# SCH_GesPot_2025-03-14.net
KiCad netlist of a schematic drawn in EasyEDA
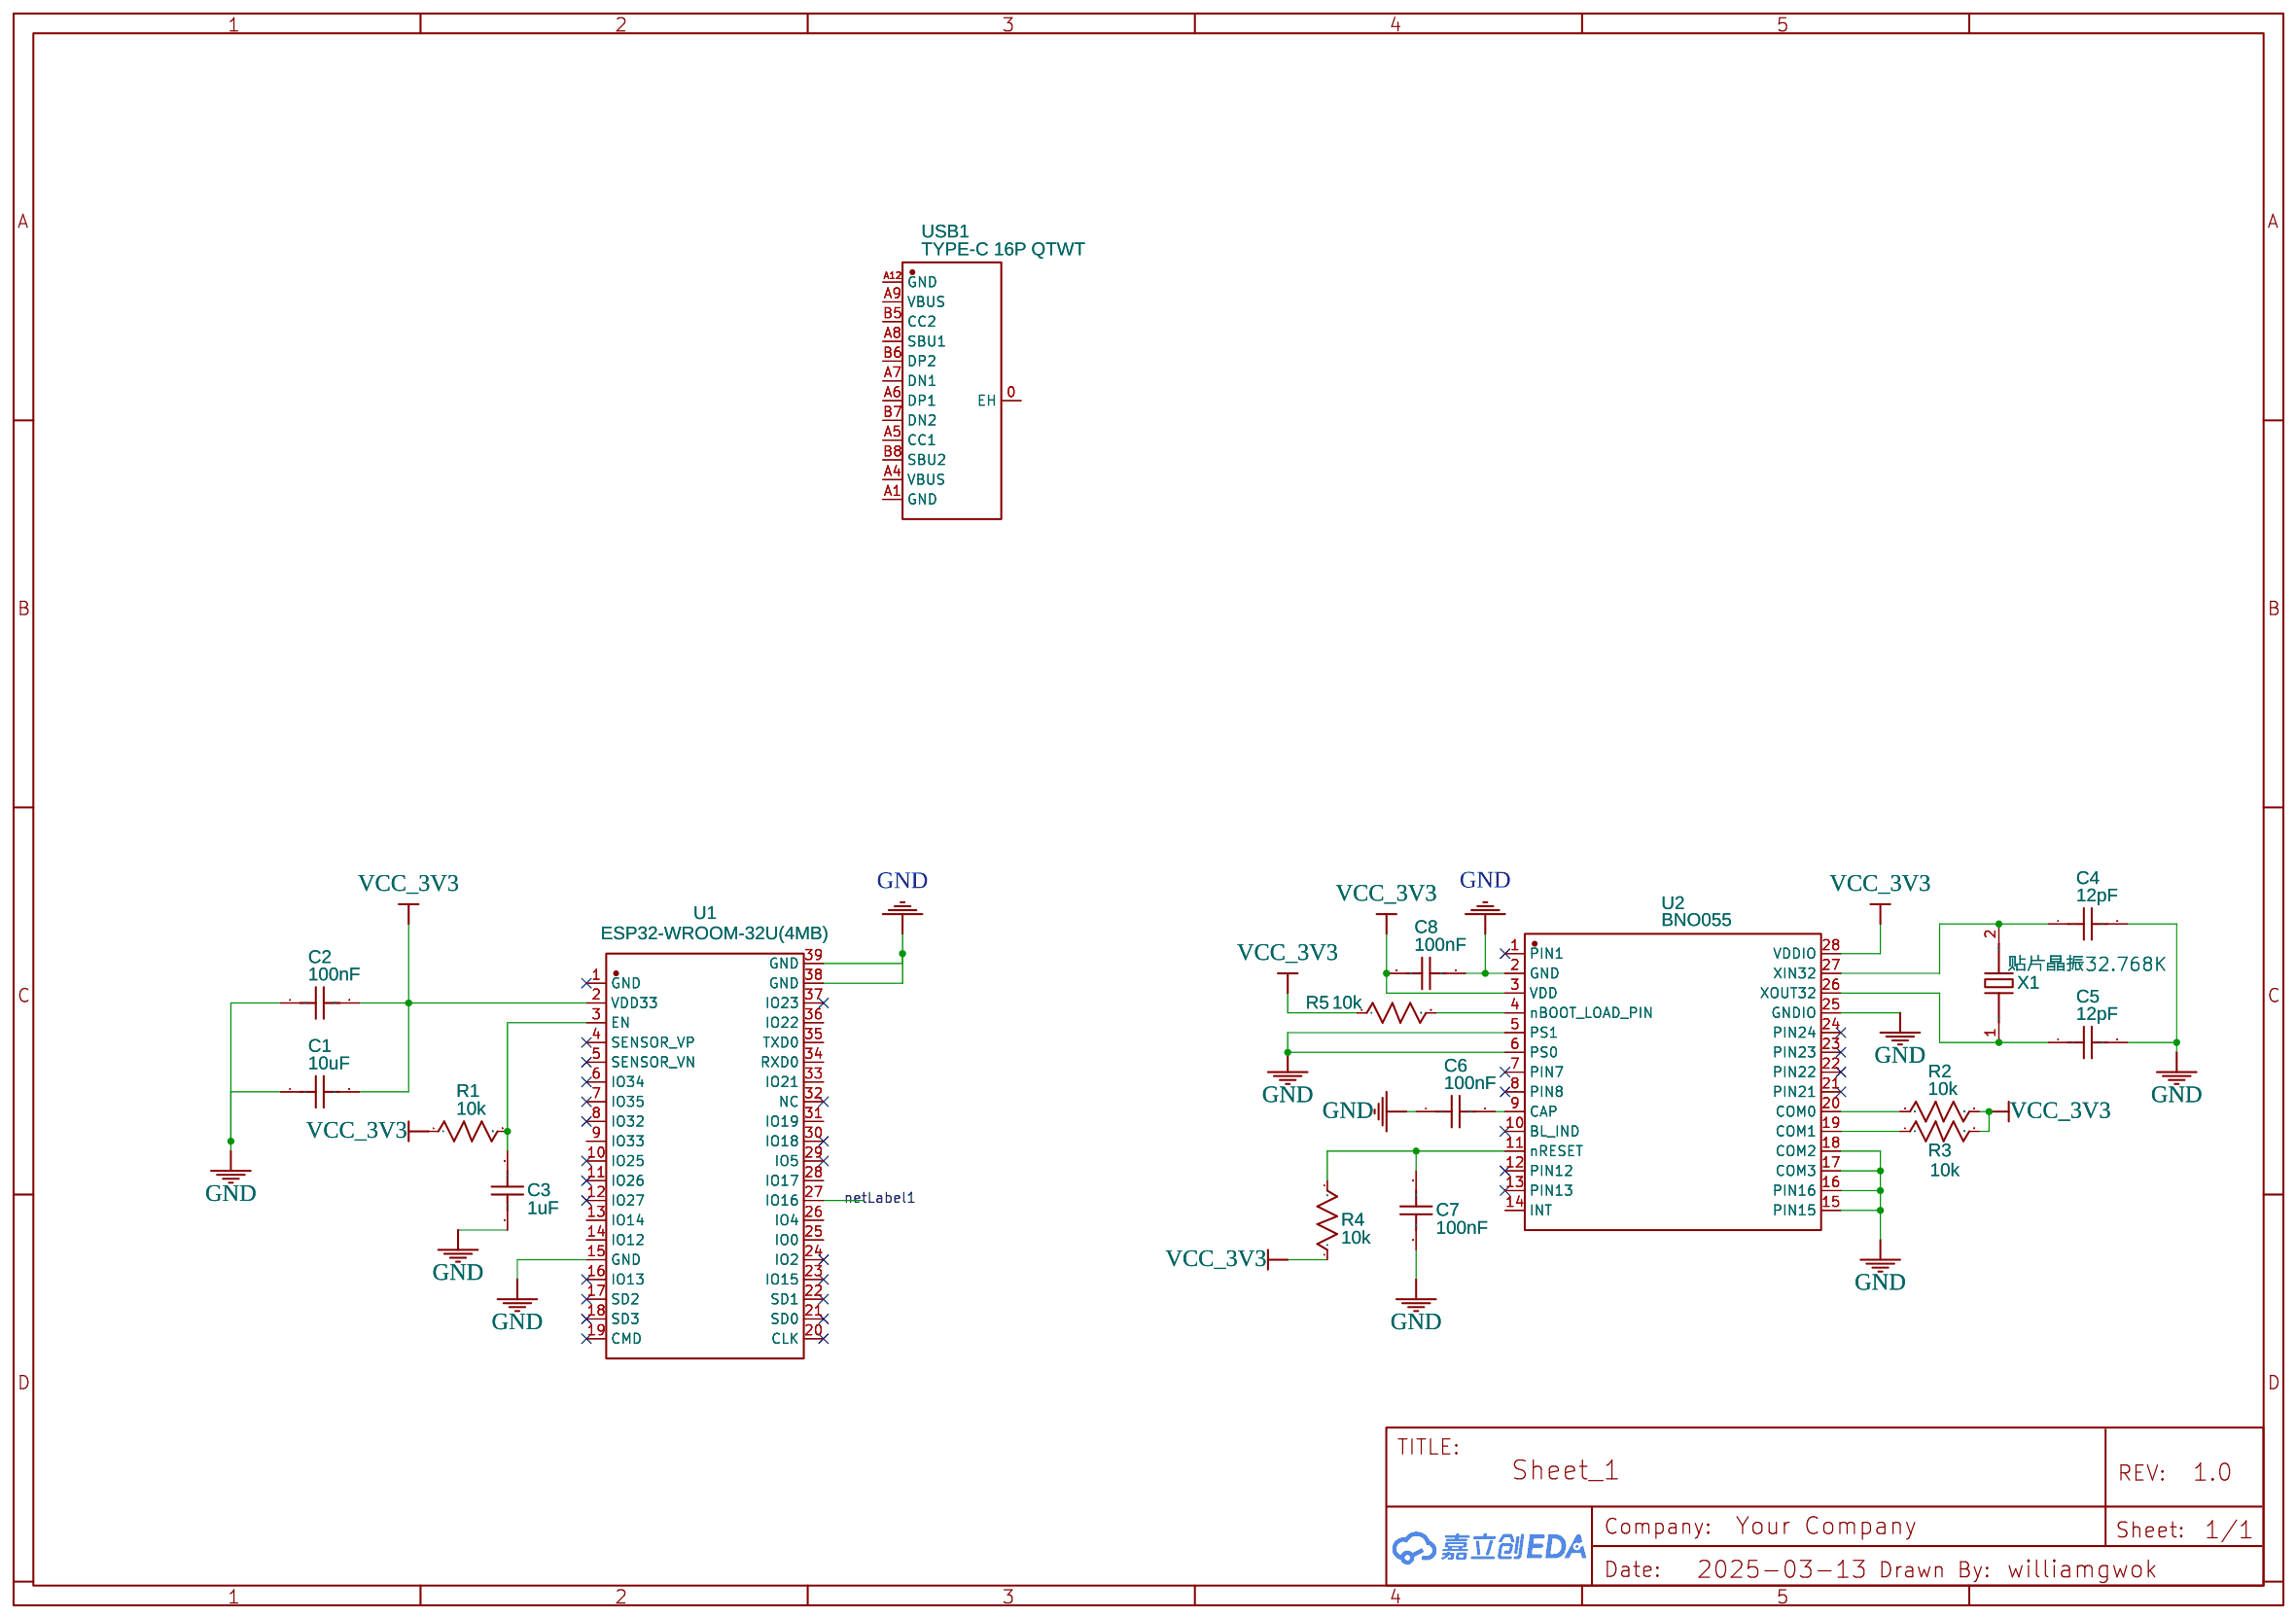
[diagram p0: schematic sheet]

(export (version "E")
  (design (tool "Eeschema 10.0.6"))
  (components
    (comp (ref "C1") (value "10uF") (libsource (lib "") (part "C_0603_US")))
    (comp (ref "C2") (value "100nF") (libsource (lib "") (part "C_0603_US")))
    (comp (ref "C3") (value "1uF") (libsource (lib "") (part "C_0603_US_2")))
    (comp (ref "C4") (value "12pF") (libsource (lib "") (part "C_0603_US")))
    (comp (ref "C5") (value "12pF") (libsource (lib "") (part "C_0603_US")))
    (comp (ref "C6") (value "100nF") (libsource (lib "") (part "C_0603_US")))
    (comp (ref "C7") (value "100nF") (libsource (lib "") (part "C_0603_US_2")))
    (comp (ref "C8") (value "100nF") (libsource (lib "") (part "C_0603_US_1")))
    (comp (ref "R1") (value "10k") (libsource (lib "") (part "R_0603_US")))
    (comp (ref "R2") (value "10k") (libsource (lib "") (part "R_0603_US")))
    (comp (ref "R3") (value "10k") (libsource (lib "") (part "R_0603_US")))
    (comp (ref "R4") (value "10k") (libsource (lib "") (part "R_0603_US_1")))
    (comp (ref "R5") (value "10k") (libsource (lib "") (part "R_0603_US")))
    (comp (ref "U1")
      (value "ESP32-WROOM-32U(4MB)")
      (fields (field (name "Manufacturer") "ESPRESSIF(乐鑫)"))
      (libsource (lib "") (part "ESP32-WROOM-32U(4MB)"))
    )
    (comp (ref "U2")
      (value "BNO055")
      (fields (field (name "Manufacturer") "Bosch(博世)"))
      (libsource (lib "") (part "BNO055"))
    )
    (comp (ref "USB1")
      (value "TYPE-C 16P QTWT")
      (fields (field (name "Manufacturer") "SHOU HAN(首韩)"))
      (libsource (lib "") (part "TYPE-C 16P QTWT"))
    )
    (comp (ref "X1")
      (value "贴片晶振32.768K")
      (fields (field (name "Manufacturer Part") "贴片晶振32.768k"))
      (libsource (lib "") (part "贴片晶振32.768K"))
    )
  )
  (nets
    (net (code "1") (name "/netLabel1") (class "Default")
      (node (ref "U1") (pin "27") (pinfunction "IO16_27") (pintype "unspecified"))
    )
    (net (code "2") (name "GND") (class "Default")
      (node (ref "C1") (pin "1") (pinfunction "1_1") (pintype "unspecified"))
      (node (ref "C2") (pin "1") (pinfunction "1_1") (pintype "unspecified"))
      (node (ref "C3") (pin "1") (pinfunction "1_1") (pintype "unspecified"))
      (node (ref "C4") (pin "2") (pinfunction "2_2") (pintype "unspecified"))
      (node (ref "C5") (pin "2") (pinfunction "2_2") (pintype "unspecified"))
      (node (ref "C6") (pin "1") (pinfunction "1_1") (pintype "unspecified"))
      (node (ref "C7") (pin "1") (pinfunction "1_1") (pintype "unspecified"))
      (node (ref "C8") (pin "1") (pinfunction "1_1") (pintype "unspecified"))
      (node (ref "U1") (pin "15") (pinfunction "GND_15") (pintype "unspecified"))
      (node (ref "U1") (pin "38") (pinfunction "GND_38") (pintype "unspecified"))
      (node (ref "U1") (pin "39") (pinfunction "GND_39") (pintype "unspecified"))
      (node (ref "U2") (pin "15") (pinfunction "PIN15_15") (pintype "unspecified"))
      (node (ref "U2") (pin "16") (pinfunction "PIN16_16") (pintype "unspecified"))
      (node (ref "U2") (pin "17") (pinfunction "COM3_17") (pintype "unspecified"))
      (node (ref "U2") (pin "18") (pinfunction "COM2_18") (pintype "unspecified"))
      (node (ref "U2") (pin "2") (pinfunction "GND_2") (pintype "unspecified"))
      (node (ref "U2") (pin "25") (pinfunction "GNDIO_25") (pintype "unspecified"))
      (node (ref "U2") (pin "5") (pinfunction "PS1_5") (pintype "unspecified"))
      (node (ref "U2") (pin "6") (pinfunction "PS0_6") (pintype "unspecified"))
    )
    (net (code "3") (name "Net-(U1-EN)") (class "Default")
      (node (ref "C3") (pin "2") (pinfunction "2_2") (pintype "unspecified"))
      (node (ref "R1") (pin "2") (pinfunction "2_2") (pintype "unspecified"))
      (node (ref "U1") (pin "3") (pinfunction "EN_3") (pintype "unspecified"))
    )
    (net (code "4") (name "Net-(U2-CAP)") (class "Default")
      (node (ref "C6") (pin "2") (pinfunction "2_2") (pintype "unspecified"))
      (node (ref "U2") (pin "9") (pinfunction "CAP_9") (pintype "unspecified"))
    )
    (net (code "5") (name "Net-(U2-COM0)") (class "Default")
      (node (ref "R2") (pin "1") (pinfunction "1_1") (pintype "unspecified"))
      (node (ref "U2") (pin "20") (pinfunction "COM0_20") (pintype "unspecified"))
    )
    (net (code "6") (name "Net-(U2-COM1)") (class "Default")
      (node (ref "R3") (pin "1") (pinfunction "1_1") (pintype "unspecified"))
      (node (ref "U2") (pin "19") (pinfunction "COM1_19") (pintype "unspecified"))
    )
    (net (code "7") (name "Net-(U2-XIN32)") (class "Default")
      (node (ref "C4") (pin "1") (pinfunction "1_1") (pintype "unspecified"))
      (node (ref "U2") (pin "27") (pinfunction "XIN32_27") (pintype "unspecified"))
      (node (ref "X1") (pin "2") (pinfunction "2_2") (pintype "input"))
    )
    (net (code "8") (name "Net-(U2-XOUT32)") (class "Default")
      (node (ref "C5") (pin "1") (pinfunction "1_1") (pintype "unspecified"))
      (node (ref "U2") (pin "26") (pinfunction "XOUT32_26") (pintype "unspecified"))
      (node (ref "X1") (pin "1") (pinfunction "1_1") (pintype "input"))
    )
    (net (code "9") (name "Net-(U2-nBOOT_LOAD_PIN)") (class "Default")
      (node (ref "R5") (pin "2") (pinfunction "2_2") (pintype "unspecified"))
      (node (ref "U2") (pin "4") (pinfunction "nBOOT_LOAD_PIN_4") (pintype "unspecified"))
    )
    (net (code "10") (name "Net-(U2-nRESET)") (class "Default")
      (node (ref "C7") (pin "2") (pinfunction "2_2") (pintype "unspecified"))
      (node (ref "R4") (pin "2") (pinfunction "2_2") (pintype "unspecified"))
      (node (ref "U2") (pin "11") (pinfunction "nRESET_11") (pintype "unspecified"))
    )
    (net (code "11") (name "VCC_3V3") (class "Default")
      (node (ref "C1") (pin "2") (pinfunction "2_2") (pintype "unspecified"))
      (node (ref "C2") (pin "2") (pinfunction "2_2") (pintype "unspecified"))
      (node (ref "C8") (pin "2") (pinfunction "2_2") (pintype "unspecified"))
      (node (ref "R1") (pin "1") (pinfunction "1_1") (pintype "unspecified"))
      (node (ref "R2") (pin "2") (pinfunction "2_2") (pintype "unspecified"))
      (node (ref "R3") (pin "2") (pinfunction "2_2") (pintype "unspecified"))
      (node (ref "R4") (pin "1") (pinfunction "1_1") (pintype "unspecified"))
      (node (ref "R5") (pin "1") (pinfunction "1_1") (pintype "unspecified"))
      (node (ref "U1") (pin "2") (pinfunction "VDD33_2") (pintype "unspecified"))
      (node (ref "U2") (pin "28") (pinfunction "VDDIO_28") (pintype "unspecified"))
      (node (ref "U2") (pin "3") (pinfunction "VDD_3") (pintype "unspecified"))
    )
    (net (code "12") (name "unconnected-(U1-CLK-Pad20)") (class "Default")
      (node (ref "U1") (pin "20") (pinfunction "CLK_20") (pintype "unspecified+no_connect"))
    )
    (net (code "13") (name "unconnected-(U1-CMD-Pad19)") (class "Default")
      (node (ref "U1") (pin "19") (pinfunction "CMD_19") (pintype "unspecified+no_connect"))
    )
    (net (code "14") (name "unconnected-(U1-GND-Pad1)") (class "Default")
      (node (ref "U1") (pin "1") (pinfunction "GND_1") (pintype "unspecified+no_connect"))
    )
    (net (code "15") (name "unconnected-(U1-IO0-Pad25)") (class "Default")
      (node (ref "U1") (pin "25") (pinfunction "IO0_25") (pintype "unspecified"))
    )
    (net (code "16") (name "unconnected-(U1-IO2-Pad24)") (class "Default")
      (node (ref "U1") (pin "24") (pinfunction "IO2_24") (pintype "unspecified+no_connect"))
    )
    (net (code "17") (name "unconnected-(U1-IO4-Pad26)") (class "Default")
      (node (ref "U1") (pin "26") (pinfunction "IO4_26") (pintype "unspecified"))
    )
    (net (code "18") (name "unconnected-(U1-IO5-Pad29)") (class "Default")
      (node (ref "U1") (pin "29") (pinfunction "IO5_29") (pintype "unspecified+no_connect"))
    )
    (net (code "19") (name "unconnected-(U1-IO12-Pad14)") (class "Default")
      (node (ref "U1") (pin "14") (pinfunction "IO12_14") (pintype "unspecified"))
    )
    (net (code "20") (name "unconnected-(U1-IO13-Pad16)") (class "Default")
      (node (ref "U1") (pin "16") (pinfunction "IO13_16") (pintype "unspecified+no_connect"))
    )
    (net (code "21") (name "unconnected-(U1-IO14-Pad13)") (class "Default")
      (node (ref "U1") (pin "13") (pinfunction "IO14_13") (pintype "unspecified"))
    )
    (net (code "22") (name "unconnected-(U1-IO15-Pad23)") (class "Default")
      (node (ref "U1") (pin "23") (pinfunction "IO15_23") (pintype "unspecified+no_connect"))
    )
    (net (code "23") (name "unconnected-(U1-IO17-Pad28)") (class "Default")
      (node (ref "U1") (pin "28") (pinfunction "IO17_28") (pintype "unspecified"))
    )
    (net (code "24") (name "unconnected-(U1-IO18-Pad30)") (class "Default")
      (node (ref "U1") (pin "30") (pinfunction "IO18_30") (pintype "unspecified+no_connect"))
    )
    (net (code "25") (name "unconnected-(U1-IO19-Pad31)") (class "Default")
      (node (ref "U1") (pin "31") (pinfunction "IO19_31") (pintype "unspecified"))
    )
    (net (code "26") (name "unconnected-(U1-IO21-Pad33)") (class "Default")
      (node (ref "U1") (pin "33") (pinfunction "IO21_33") (pintype "unspecified"))
    )
    (net (code "27") (name "unconnected-(U1-IO22-Pad36)") (class "Default")
      (node (ref "U1") (pin "36") (pinfunction "IO22_36") (pintype "unspecified"))
    )
    (net (code "28") (name "unconnected-(U1-IO23-Pad37)") (class "Default")
      (node (ref "U1") (pin "37") (pinfunction "IO23_37") (pintype "unspecified+no_connect"))
    )
    (net (code "29") (name "unconnected-(U1-IO25-Pad10)") (class "Default")
      (node (ref "U1") (pin "10") (pinfunction "IO25_10") (pintype "unspecified+no_connect"))
    )
    (net (code "30") (name "unconnected-(U1-IO26-Pad11)") (class "Default")
      (node (ref "U1") (pin "11") (pinfunction "IO26_11") (pintype "unspecified+no_connect"))
    )
    (net (code "31") (name "unconnected-(U1-IO27-Pad12)") (class "Default")
      (node (ref "U1") (pin "12") (pinfunction "IO27_12") (pintype "unspecified+no_connect"))
    )
    (net (code "32") (name "unconnected-(U1-IO32-Pad8)") (class "Default")
      (node (ref "U1") (pin "8") (pinfunction "IO32_8") (pintype "unspecified+no_connect"))
    )
    (net (code "33") (name "unconnected-(U1-IO33-Pad9)") (class "Default")
      (node (ref "U1") (pin "9") (pinfunction "IO33_9") (pintype "unspecified"))
    )
    (net (code "34") (name "unconnected-(U1-IO34-Pad6)") (class "Default")
      (node (ref "U1") (pin "6") (pinfunction "IO34_6") (pintype "unspecified+no_connect"))
    )
    (net (code "35") (name "unconnected-(U1-IO35-Pad7)") (class "Default")
      (node (ref "U1") (pin "7") (pinfunction "IO35_7") (pintype "unspecified+no_connect"))
    )
    (net (code "36") (name "unconnected-(U1-NC-Pad32)") (class "Default")
      (node (ref "U1") (pin "32") (pinfunction "NC_32") (pintype "unspecified+no_connect"))
    )
    (net (code "37") (name "unconnected-(U1-RXD0-Pad34)") (class "Default")
      (node (ref "U1") (pin "34") (pinfunction "RXD0_34") (pintype "unspecified"))
    )
    (net (code "38") (name "unconnected-(U1-SD0-Pad21)") (class "Default")
      (node (ref "U1") (pin "21") (pinfunction "SD0_21") (pintype "unspecified+no_connect"))
    )
    (net (code "39") (name "unconnected-(U1-SD1-Pad22)") (class "Default")
      (node (ref "U1") (pin "22") (pinfunction "SD1_22") (pintype "unspecified+no_connect"))
    )
    (net (code "40") (name "unconnected-(U1-SD2-Pad17)") (class "Default")
      (node (ref "U1") (pin "17") (pinfunction "SD2_17") (pintype "unspecified+no_connect"))
    )
    (net (code "41") (name "unconnected-(U1-SD3-Pad18)") (class "Default")
      (node (ref "U1") (pin "18") (pinfunction "SD3_18") (pintype "unspecified+no_connect"))
    )
    (net (code "42") (name "unconnected-(U1-SENSOR_VN-Pad5)") (class "Default")
      (node (ref "U1") (pin "5") (pinfunction "SENSOR_VN_5") (pintype "unspecified+no_connect"))
    )
    (net (code "43") (name "unconnected-(U1-SENSOR_VP-Pad4)") (class "Default")
      (node (ref "U1") (pin "4") (pinfunction "SENSOR_VP_4") (pintype "unspecified+no_connect"))
    )
    (net (code "44") (name "unconnected-(U1-TXD0-Pad35)") (class "Default")
      (node (ref "U1") (pin "35") (pinfunction "TXD0_35") (pintype "unspecified"))
    )
    (net (code "45") (name "unconnected-(U2-BL_IND-Pad10)") (class "Default")
      (node (ref "U2") (pin "10") (pinfunction "BL_IND_10") (pintype "unspecified+no_connect"))
    )
    (net (code "46") (name "unconnected-(U2-INT-Pad14)") (class "Default")
      (node (ref "U2") (pin "14") (pinfunction "INT_14") (pintype "unspecified"))
    )
    (net (code "47") (name "unconnected-(U2-PIN1-Pad1)") (class "Default")
      (node (ref "U2") (pin "1") (pinfunction "PIN1_1") (pintype "unspecified+no_connect"))
    )
    (net (code "48") (name "unconnected-(U2-PIN7-Pad7)") (class "Default")
      (node (ref "U2") (pin "7") (pinfunction "PIN7_7") (pintype "unspecified+no_connect"))
    )
    (net (code "49") (name "unconnected-(U2-PIN8-Pad8)") (class "Default")
      (node (ref "U2") (pin "8") (pinfunction "PIN8_8") (pintype "unspecified+no_connect"))
    )
    (net (code "50") (name "unconnected-(U2-PIN12-Pad12)") (class "Default")
      (node (ref "U2") (pin "12") (pinfunction "PIN12_12") (pintype "unspecified+no_connect"))
    )
    (net (code "51") (name "unconnected-(U2-PIN13-Pad13)") (class "Default")
      (node (ref "U2") (pin "13") (pinfunction "PIN13_13") (pintype "unspecified+no_connect"))
    )
    (net (code "52") (name "unconnected-(U2-PIN21-Pad21)") (class "Default")
      (node (ref "U2") (pin "21") (pinfunction "PIN21_21") (pintype "unspecified+no_connect"))
    )
    (net (code "53") (name "unconnected-(U2-PIN22-Pad22)") (class "Default")
      (node (ref "U2") (pin "22") (pinfunction "PIN22_22") (pintype "unspecified+no_connect"))
    )
    (net (code "54") (name "unconnected-(U2-PIN23-Pad23)") (class "Default")
      (node (ref "U2") (pin "23") (pinfunction "PIN23_23") (pintype "unspecified+no_connect"))
    )
    (net (code "55") (name "unconnected-(U2-PIN24-Pad24)") (class "Default")
      (node (ref "U2") (pin "24") (pinfunction "PIN24_24") (pintype "unspecified+no_connect"))
    )
    (net (code "56") (name "unconnected-(USB1-CC1-PadA5)") (class "Default")
      (node (ref "USB1") (pin "A5") (pinfunction "CC1_A5") (pintype "unspecified"))
    )
    (net (code "57") (name "unconnected-(USB1-CC2-PadB5)") (class "Default")
      (node (ref "USB1") (pin "B5") (pinfunction "CC2_B5") (pintype "unspecified"))
    )
    (net (code "58") (name "unconnected-(USB1-DN1-PadA7)") (class "Default")
      (node (ref "USB1") (pin "A7") (pinfunction "DN1_A7") (pintype "unspecified"))
    )
    (net (code "59") (name "unconnected-(USB1-DN2-PadB7)") (class "Default")
      (node (ref "USB1") (pin "B7") (pinfunction "DN2_B7") (pintype "unspecified"))
    )
    (net (code "60") (name "unconnected-(USB1-DP1-PadA6)") (class "Default")
      (node (ref "USB1") (pin "A6") (pinfunction "DP1_A6") (pintype "unspecified"))
    )
    (net (code "61") (name "unconnected-(USB1-DP2-PadB6)") (class "Default")
      (node (ref "USB1") (pin "B6") (pinfunction "DP2_B6") (pintype "unspecified"))
    )
    (net (code "62") (name "unconnected-(USB1-EH-Pad0)") (class "Default")
      (node (ref "USB1") (pin "0") (pinfunction "EH_0") (pintype "unspecified"))
    )
    (net (code "63") (name "unconnected-(USB1-GND-PadA1)") (class "Default")
      (node (ref "USB1") (pin "A1") (pinfunction "GND_A1") (pintype "unspecified"))
    )
    (net (code "64") (name "unconnected-(USB1-GND-PadA12)") (class "Default")
      (node (ref "USB1") (pin "A12") (pinfunction "GND_A12") (pintype "unspecified"))
    )
    (net (code "65") (name "unconnected-(USB1-SBU1-PadA8)") (class "Default")
      (node (ref "USB1") (pin "A8") (pinfunction "SBU1_A8") (pintype "unspecified"))
    )
    (net (code "66") (name "unconnected-(USB1-SBU2-PadB8)") (class "Default")
      (node (ref "USB1") (pin "B8") (pinfunction "SBU2_B8") (pintype "unspecified"))
    )
    (net (code "67") (name "unconnected-(USB1-VBUS-PadA4)") (class "Default")
      (node (ref "USB1") (pin "A4") (pinfunction "VBUS_A4") (pintype "unspecified"))
    )
    (net (code "68") (name "unconnected-(USB1-VBUS-PadA9)") (class "Default")
      (node (ref "USB1") (pin "A9") (pinfunction "VBUS_A9") (pintype "unspecified"))
    )
  )
)
